# LCL_2.net
KiCad netlist of a schematic drawn in Altium Designer
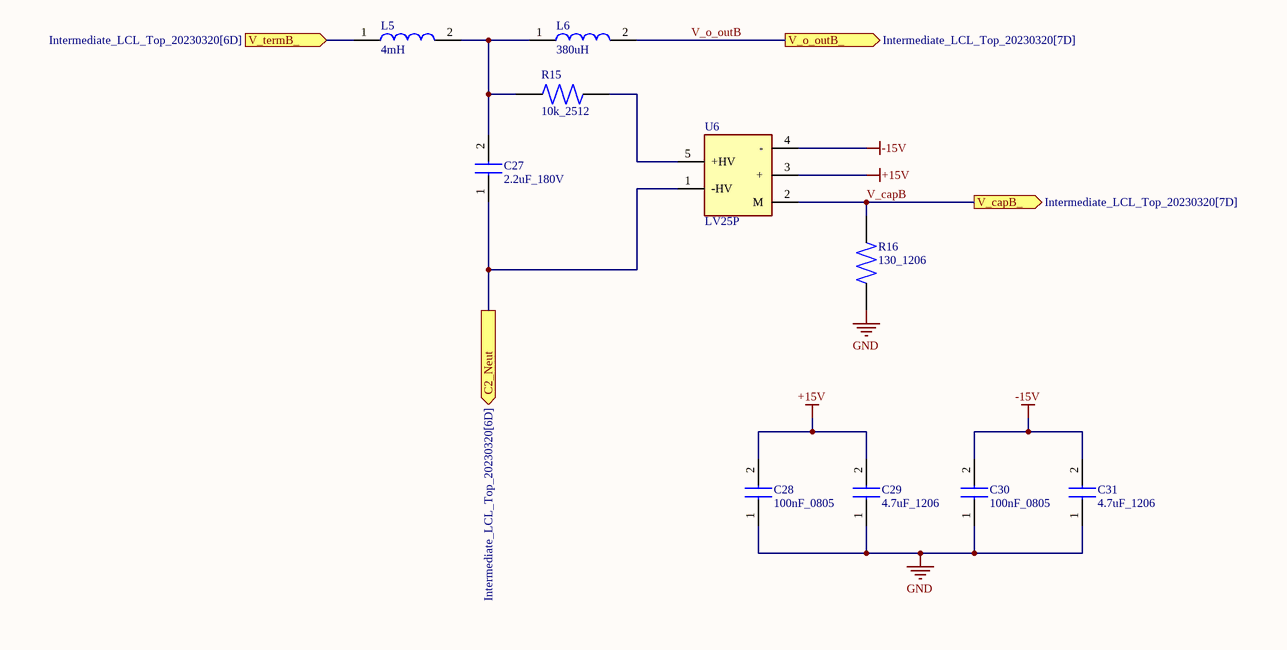
[diagram p0: LCL_2.SchDoc]

(export (version "E")
  (design (tool "Eeschema 10.0.6"))
  (components
    (comp (ref "C27")
      (value "2.2uF_180V")
      (footprint "Film Capacitor PHE450HF7220JR06L2")
      (description "KEMET PHE450 Metallised Polypropylene Film Capacitor, 180 V ac, 250 V dc, ±5%, 2.2μF, Through Hole")
      (fields (field (name "MANUFACTURER_PART_NUMBER") "PHE450HF7220JR06L2"))
      (libsource (lib "FYP_Components") (part "PHE450HF7220JR06L2"))
    )
    (comp (ref "C28")
      (value "100nF_0805")
      (footprint "0805 Capacitor")
      (description "SMD Multilayer Ceramic Capacitor, 0.1 µF, 50 V, 0805 [2012 Metric], ± 5%, X7R, C Series KEMET")
      (libsource (lib "FYP_Components") (part "C0805C104J5RACTU"))
    )
    (comp (ref "C29")
      (value "4.7uF_1206")
      (footprint "FYP_Components:1206 Capacitor")
      (description "SMD Multilayer Ceramic Capacitor, 4.7 µF, 50 V, 1206 [3216 Metric], ± 10%, X7R, C")
      (fields (field (name "MP") "C1206C120J5GACTU"))
      (libsource (lib "FYP_Components") (part "C3216X7R1H475K160AC"))
    )
    (comp (ref "C30")
      (value "100nF_0805")
      (footprint "0805 Capacitor")
      (description "SMD Multilayer Ceramic Capacitor, 0.1 µF, 50 V, 0805 [2012 Metric], ± 5%, X7R, C Series KEMET")
      (libsource (lib "FYP_Components") (part "C0805C104J5RACTU"))
    )
    (comp (ref "C31")
      (value "4.7uF_1206")
      (footprint "FYP_Components:1206 Capacitor")
      (description "SMD Multilayer Ceramic Capacitor, 4.7 µF, 50 V, 1206 [3216 Metric], ± 10%, X7R, C")
      (fields (field (name "MP") "C1206C120J5GACTU"))
      (libsource (lib "FYP_Components") (part "C3216X7R1H475K160AC"))
    )
    (comp (ref "L5")
      (value "4mH")
      (footprint "4mH Custom")
      (libsource (lib "FYP_Components") (part "4mH Custom Inductor"))
    )
    (comp (ref "L6")
      (value "380uH")
      (footprint "380uH Custom")
      (libsource (lib "FYP_Components") (part "380uH Custom Inductor"))
    )
    (comp (ref "R15")
      (value "10k_2512")
      (footprint "FYP_Components:2512 Resistor")
      (description "SMD Chip Resistor, 10 kohm, ± 1%, 2 W, 2512 [6432 Metric], Thick Film, High Power")
      (fields (field (name "MF") "Bourns") (field (name "MP") "CRE2512-FZ-R007E-3"))
      (libsource (lib "FYP_Components") (part "MCHP122WF1002T4E"))
    )
    (comp (ref "R16")
      (value "130_1206")
      (footprint "FYP_Components:1206 Resistor")
      (description "SMD Chip Resistor, 130 ohm, ± 1%, 250 mW, 1206 [3216 Metric], Thick Film, General Purpose")
      (fields (field (name "MF") "Bourns") (field (name "MP") "CRE2512-FZ-R007E-3"))
      (libsource (lib "FYP_Components") (part "CRCW1206130RFKEA"))
    )
    (comp (ref "U6")
      (value "LV25P")
      (footprint "FYP_Components:LV-25-P")
      (description "Undefined or Miscellaneous")
      (libsource (lib "FYP_Components") (part "LV25P"))
    )
  )
  (nets
    (net (code "1") (name "+15V") (class "Default")
      (node (ref "C28") (pin "2") (pinfunction "2_2") (pintype "passive"))
      (node (ref "C29") (pin "2") (pinfunction "2_2") (pintype "passive"))
      (node (ref "U6") (pin "3") (pinfunction "+_3") (pintype "passive"))
    )
    (net (code "2") (name "-15V") (class "Default")
      (node (ref "C30") (pin "2") (pinfunction "2_2") (pintype "passive"))
      (node (ref "C31") (pin "2") (pinfunction "2_2") (pintype "passive"))
      (node (ref "U6") (pin "4") (pinfunction "-_4") (pintype "passive"))
    )
    (net (code "3") (name "/C2_Neut") (class "Default")
      (node (ref "C27") (pin "1") (pinfunction "1_1") (pintype "passive"))
      (node (ref "U6") (pin "1") (pinfunction "-HV_1") (pintype "passive"))
    )
    (net (code "4") (name "/V_capB") (class "Default")
      (node (ref "R16") (pin "2") (pinfunction "2_2") (pintype "passive"))
      (node (ref "U6") (pin "2") (pinfunction "M_2") (pintype "passive"))
    )
    (net (code "5") (name "/V_o_outB") (class "Default")
      (node (ref "L6") (pin "2") (pinfunction "2_2") (pintype "passive"))
    )
    (net (code "6") (name "/V_termB_") (class "Default")
      (node (ref "L5") (pin "1") (pinfunction "1_1") (pintype "passive"))
    )
    (net (code "7") (name "GND") (class "Default")
      (node (ref "C28") (pin "1") (pinfunction "1_1") (pintype "passive"))
      (node (ref "C29") (pin "1") (pinfunction "1_1") (pintype "passive"))
      (node (ref "C30") (pin "1") (pinfunction "1_1") (pintype "passive"))
      (node (ref "C31") (pin "1") (pinfunction "1_1") (pintype "passive"))
      (node (ref "R16") (pin "1") (pinfunction "1_1") (pintype "passive"))
    )
    (net (code "8") (name "Net-(C27-Pad2)") (class "Default")
      (node (ref "C27") (pin "2") (pinfunction "2_2") (pintype "passive"))
      (node (ref "L5") (pin "2") (pinfunction "2_2") (pintype "passive"))
      (node (ref "L6") (pin "1") (pinfunction "1_1") (pintype "passive"))
      (node (ref "R15") (pin "1") (pinfunction "1_1") (pintype "passive"))
    )
    (net (code "9") (name "Net-(U6-+HV)") (class "Default")
      (node (ref "R15") (pin "2") (pinfunction "2_2") (pintype "passive"))
      (node (ref "U6") (pin "5") (pinfunction "+HV_5") (pintype "passive"))
    )
  )
)
